# Power.net
KiCad netlist of a schematic drawn in Altium Designer
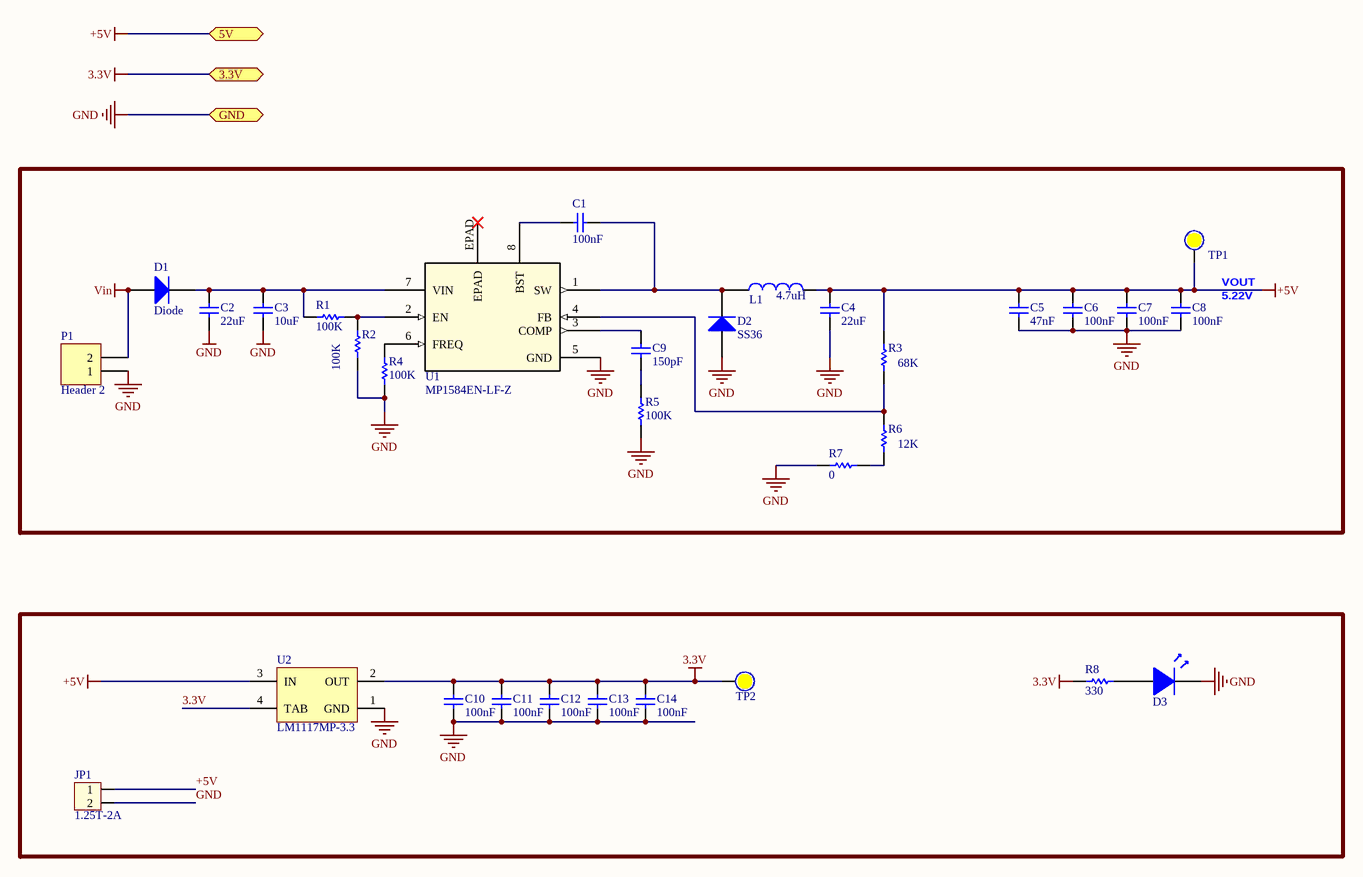
[diagram p0: Power.SchDoc]

(export (version "E")
  (design (tool "Eeschema 10.0.6"))
  (components
    (comp (ref "C1")
      (value "100nF")
      (footprint "CAPC-0402 (0506)")
      (libsource (lib "Schlib_hung") (part "TU THUONG"))
    )
    (comp (ref "C2")
      (value "22uF")
      (footprint "2012[0805]")
      (libsource (lib "Schlib_hung") (part "TU THUONG"))
    )
    (comp (ref "C3")
      (value "10uF")
      (footprint "2012[0805]")
      (libsource (lib "Schlib_hung") (part "TU THUONG"))
    )
    (comp (ref "C4")
      (value "22uF")
      (footprint "2012[0805]")
      (libsource (lib "Schlib_hung") (part "TU THUONG"))
    )
    (comp (ref "C5")
      (value "47nF")
      (footprint "2012[0805]")
      (libsource (lib "Schlib_hung") (part "TU THUONG"))
    )
    (comp (ref "C6")
      (value "100nF")
      (footprint "CAPC-0402 (0506)")
      (libsource (lib "Schlib_hung") (part "TU THUONG"))
    )
    (comp (ref "C7")
      (value "100nF")
      (footprint "CAPC-0402 (0506)")
      (libsource (lib "Schlib_hung") (part "TU THUONG"))
    )
    (comp (ref "C8")
      (value "100nF")
      (footprint "CAPC-0402 (0506)")
      (libsource (lib "Schlib_hung") (part "TU THUONG"))
    )
    (comp (ref "C9")
      (value "150pF")
      (footprint "1005[0402]")
      (libsource (lib "Schlib_hung") (part "TU THUONG"))
    )
    (comp (ref "C10")
      (value "100nF")
      (footprint "CAPC-0402 (0506)")
      (libsource (lib "Schlib_hung") (part "TU THUONG"))
    )
    (comp (ref "C11")
      (value "100nF")
      (footprint "CAPC-0402 (0506)")
      (libsource (lib "Schlib_hung") (part "TU THUONG"))
    )
    (comp (ref "C12")
      (value "100nF")
      (footprint "CAPC-0402 (0506)")
      (libsource (lib "Schlib_hung") (part "TU THUONG"))
    )
    (comp (ref "C13")
      (value "100nF")
      (footprint "CAPC-0402 (0506)")
      (libsource (lib "Schlib_hung") (part "TU THUONG"))
    )
    (comp (ref "C14")
      (value "100nF")
      (footprint "CAPC-0402 (0506)")
      (libsource (lib "Schlib_hung") (part "TU THUONG"))
    )
    (comp (ref "D1") (value "Diode") (footprint "DIODE SMD") (libsource (lib "EmbeddedLib") (part "Diode")))
    (comp (ref "D2")
      (value "SS36")
      (footprint "SMB")
      (description "Default Diode")
      (fields (field (name "PUBLISHER") "Altium Limited"))
      (libsource (lib "Integrated_Library_hung") (part "Diode"))
    )
    (comp (ref "D3") (value "LED") (footprint "LED_0603_BLUE") (libsource (lib "EmbeddedLib") (part "LED")))
    (comp (ref "JP1")
      (value "1.25T-2A")
      (footprint "BM02B-GHS")
      (description "Cắm")
      (libsource (lib "THU VIEN SCH") (part "Header 1_2.54_2P"))
    )
    (comp (ref "L1")
      (value "4.7uH")
      (footprint "INDUCTOR SMD 7x7")
      (libsource (lib "Schlib_hung") (part "Inductor SMD"))
    )
    (comp (ref "P1")
      (value "Header 2")
      (footprint "BM02B-GHS")
      (description "Header, 2-Pin")
      (fields (field (name "PUBLISHER") "Altium Limited"))
      (libsource (lib "Miscellaneous Connectors") (part "Header 2"))
    )
    (comp (ref "R1")
      (value "100K")
      (footprint "1005[0402]")
      (description "Resistor")
      (fields (field (name "PUBLISHER") "Altium Limited"))
      (libsource (lib "Schlib_hung") (part "Res1"))
    )
    (comp (ref "R2")
      (value "100K")
      (footprint "1005[0402]")
      (description "Resistor")
      (fields (field (name "PUBLISHER") "Altium Limited"))
      (libsource (lib "Schlib_hung") (part "Res1"))
    )
    (comp (ref "R3")
      (value "68K")
      (footprint "1005[0402]")
      (description "Resistor")
      (fields (field (name "PUBLISHER") "Altium Limited"))
      (libsource (lib "Schlib_hung") (part "Res1"))
    )
    (comp (ref "R4")
      (value "100K")
      (footprint "1005[0402]")
      (description "Resistor")
      (fields (field (name "PUBLISHER") "Altium Limited"))
      (libsource (lib "Schlib_hung") (part "Res1"))
    )
    (comp (ref "R5")
      (value "100K")
      (footprint "1005[0402]")
      (description "Resistor")
      (fields (field (name "PUBLISHER") "Altium Limited"))
      (libsource (lib "Schlib_hung") (part "Res1"))
    )
    (comp (ref "R6")
      (value "12K")
      (footprint "1005[0402]")
      (description "Resistor")
      (fields (field (name "PUBLISHER") "Altium Limited"))
      (libsource (lib "Schlib_hung") (part "Res1"))
    )
    (comp (ref "R7")
      (value "0")
      (footprint "1005[0402]")
      (description "Resistor")
      (fields (field (name "PUBLISHER") "Altium Limited"))
      (libsource (lib "Schlib_hung") (part "Res1"))
    )
    (comp (ref "R8")
      (value "330")
      (footprint "RESC-0402 (1005)")
      (description "Semiconductor Resistor")
      (fields (field (name "PUBLISHER") "Altium Limited"))
      (libsource (lib "EmbeddedLib") (part "Res Semi"))
    )
    (comp (ref "TP1")
      (value "~")
      (footprint "PCB1:Test Point 1 MM")
      (description "Test Point")
      (libsource (lib "BYTECH_HW_LIB_2019 (1)") (part "Test Point"))
    )
    (comp (ref "TP2")
      (value "~")
      (footprint "PCB1:Test Point 1 MM")
      (description "Test Point")
      (libsource (lib "") (part "Test Point_1"))
    )
    (comp (ref "U1")
      (value "MP1584EN-LF-Z")
      (footprint "SOIC8E_MPS")
      (description "No Description Available")
      (fields (field (name "COPYRIGHT") "Copyright (C) 2023 Ultra Librarian. All rights reserved."))
      (libsource (lib "Schlib_Trung") (part "MP1584EN-LF-Z"))
    )
    (comp (ref "U2")
      (value "LM1117MP-3.3")
      (footprint "MP04A_N")
      (description "800mA Low-Dropout Linear Regulator, 4-pin SOT-223")
      (fields
        (field (name "MANUFACTURER") "National Semiconductor")
        (field (name "PUBLISHER") "Altium Limited")
      )
      (libsource (lib "Integrated_Library_hung") (part "LM1117MP-3.3"))
    )
  )
  (nets
    (net (code "1") (name "+5V") (class "Default")
      (node (ref "C4") (pin "2") (pinfunction "2_2") (pintype "passive"))
      (node (ref "C5") (pin "2") (pinfunction "2_2") (pintype "passive"))
      (node (ref "C6") (pin "2") (pinfunction "2_2") (pintype "passive"))
      (node (ref "C7") (pin "2") (pinfunction "2_2") (pintype "passive"))
      (node (ref "C8") (pin "2") (pinfunction "2_2") (pintype "passive"))
      (node (ref "JP1") (pin "1") (pinfunction "1_1") (pintype "passive"))
      (node (ref "L1") (pin "2") (pinfunction "2_2") (pintype "passive"))
      (node (ref "R3") (pin "2") (pinfunction "2_2") (pintype "passive"))
      (node (ref "TP1") (pin "0") (pinfunction "0_0") (pintype "passive"))
      (node (ref "U2") (pin "3") (pinfunction "IN_3") (pintype "power_in"))
    )
    (net (code "2") (name "3.3V") (class "Default")
      (node (ref "C10") (pin "2") (pinfunction "2_2") (pintype "passive"))
      (node (ref "C11") (pin "2") (pinfunction "2_2") (pintype "passive"))
      (node (ref "C12") (pin "2") (pinfunction "2_2") (pintype "passive"))
      (node (ref "C13") (pin "2") (pinfunction "2_2") (pintype "passive"))
      (node (ref "C14") (pin "2") (pinfunction "2_2") (pintype "passive"))
      (node (ref "R8") (pin "2") (pinfunction "2_2") (pintype "passive"))
      (node (ref "TP2") (pin "0") (pinfunction "0_0") (pintype "passive"))
      (node (ref "U2") (pin "2") (pinfunction "OUT_2") (pintype "power_in"))
      (node (ref "U2") (pin "4") (pinfunction "TAB_4") (pintype "power_in"))
    )
    (net (code "3") (name "GND") (class "Default")
      (node (ref "C10") (pin "1") (pinfunction "1_1") (pintype "passive"))
      (node (ref "C11") (pin "1") (pinfunction "1_1") (pintype "passive"))
      (node (ref "C12") (pin "1") (pinfunction "1_1") (pintype "passive"))
      (node (ref "C13") (pin "1") (pinfunction "1_1") (pintype "passive"))
      (node (ref "C14") (pin "1") (pinfunction "1_1") (pintype "passive"))
      (node (ref "C2") (pin "1") (pinfunction "1_1") (pintype "passive"))
      (node (ref "C3") (pin "1") (pinfunction "1_1") (pintype "passive"))
      (node (ref "C4") (pin "1") (pinfunction "1_1") (pintype "passive"))
      (node (ref "C5") (pin "1") (pinfunction "1_1") (pintype "passive"))
      (node (ref "C6") (pin "1") (pinfunction "1_1") (pintype "passive"))
      (node (ref "C7") (pin "1") (pinfunction "1_1") (pintype "passive"))
      (node (ref "C8") (pin "1") (pinfunction "1_1") (pintype "passive"))
      (node (ref "D2") (pin "1") (pinfunction "A_1") (pintype "passive"))
      (node (ref "D3") (pin "2") (pinfunction "K_2") (pintype "passive"))
      (node (ref "JP1") (pin "2") (pinfunction "2_2") (pintype "passive"))
      (node (ref "P1") (pin "1") (pinfunction "1_1") (pintype "passive"))
      (node (ref "R2") (pin "1") (pinfunction "1_1") (pintype "passive"))
      (node (ref "R4") (pin "2") (pinfunction "2_2") (pintype "passive"))
      (node (ref "R5") (pin "2") (pinfunction "2_2") (pintype "passive"))
      (node (ref "R7") (pin "1") (pinfunction "1_1") (pintype "passive"))
      (node (ref "U1") (pin "5") (pinfunction "GND_5") (pintype "passive"))
      (node (ref "U2") (pin "1") (pinfunction "GND_1") (pintype "power_in"))
    )
    (net (code "4") (name "Net-(C9-Pad1)") (class "Default")
      (node (ref "C9") (pin "1") (pinfunction "1_1") (pintype "passive"))
      (node (ref "R5") (pin "1") (pinfunction "1_1") (pintype "passive"))
    )
    (net (code "5") (name "Net-(D1-K)") (class "Default")
      (node (ref "C2") (pin "2") (pinfunction "2_2") (pintype "passive"))
      (node (ref "C3") (pin "2") (pinfunction "2_2") (pintype "passive"))
      (node (ref "D1") (pin "2") (pinfunction "K_2") (pintype "passive"))
      (node (ref "R1") (pin "2") (pinfunction "2_2") (pintype "passive"))
      (node (ref "U1") (pin "7") (pinfunction "VIN_7") (pintype "power_in"))
    )
    (net (code "6") (name "Net-(D2-K)") (class "Default")
      (node (ref "C1") (pin "1") (pinfunction "1_1") (pintype "passive"))
      (node (ref "D2") (pin "2") (pinfunction "K_2") (pintype "passive"))
      (node (ref "L1") (pin "1") (pinfunction "1_1") (pintype "passive"))
      (node (ref "U1") (pin "1") (pinfunction "SW_1") (pintype "output"))
    )
    (net (code "7") (name "Net-(D3-A)") (class "Default")
      (node (ref "D3") (pin "1") (pinfunction "A_1") (pintype "passive"))
      (node (ref "R8") (pin "1") (pinfunction "1_1") (pintype "passive"))
    )
    (net (code "8") (name "Net-(R6-Pad2)") (class "Default")
      (node (ref "R6") (pin "2") (pinfunction "2_2") (pintype "passive"))
      (node (ref "R7") (pin "2") (pinfunction "2_2") (pintype "passive"))
    )
    (net (code "9") (name "Net-(U1-BST)") (class "Default")
      (node (ref "C1") (pin "2") (pinfunction "2_2") (pintype "passive"))
      (node (ref "U1") (pin "8") (pinfunction "BST_8") (pintype "passive"))
    )
    (net (code "10") (name "Net-(U1-COMP)") (class "Default")
      (node (ref "C9") (pin "2") (pinfunction "2_2") (pintype "passive"))
      (node (ref "U1") (pin "3") (pinfunction "COMP_3") (pintype "output"))
    )
    (net (code "11") (name "Net-(U1-EN)") (class "Default")
      (node (ref "R1") (pin "1") (pinfunction "1_1") (pintype "passive"))
      (node (ref "R2") (pin "2") (pinfunction "2_2") (pintype "passive"))
      (node (ref "U1") (pin "2") (pinfunction "EN_2") (pintype "input"))
    )
    (net (code "12") (name "Net-(U1-FB)") (class "Default")
      (node (ref "R3") (pin "1") (pinfunction "1_1") (pintype "passive"))
      (node (ref "R6") (pin "1") (pinfunction "1_1") (pintype "passive"))
      (node (ref "U1") (pin "4") (pinfunction "FB_4") (pintype "input"))
    )
    (net (code "13") (name "Net-(U1-FREQ)") (class "Default")
      (node (ref "R4") (pin "1") (pinfunction "1_1") (pintype "passive"))
      (node (ref "U1") (pin "6") (pinfunction "FREQ_6") (pintype "input"))
    )
    (net (code "14") (name "Vin") (class "Default")
      (node (ref "D1") (pin "1") (pinfunction "A_1") (pintype "passive"))
      (node (ref "P1") (pin "2") (pinfunction "2_2") (pintype "passive"))
    )
    (net (code "15") (name "unconnected-(U1-PadEPAD)") (class "Default")
      (node (ref "U1") (pin "EPAD") (pinfunction "EPAD_EPAD") (pintype "passive+no_connect"))
    )
  )
)
